# DM1090FFC_MIPI_CAM.net
KiCad netlist of a schematic drawn in Altium Designer
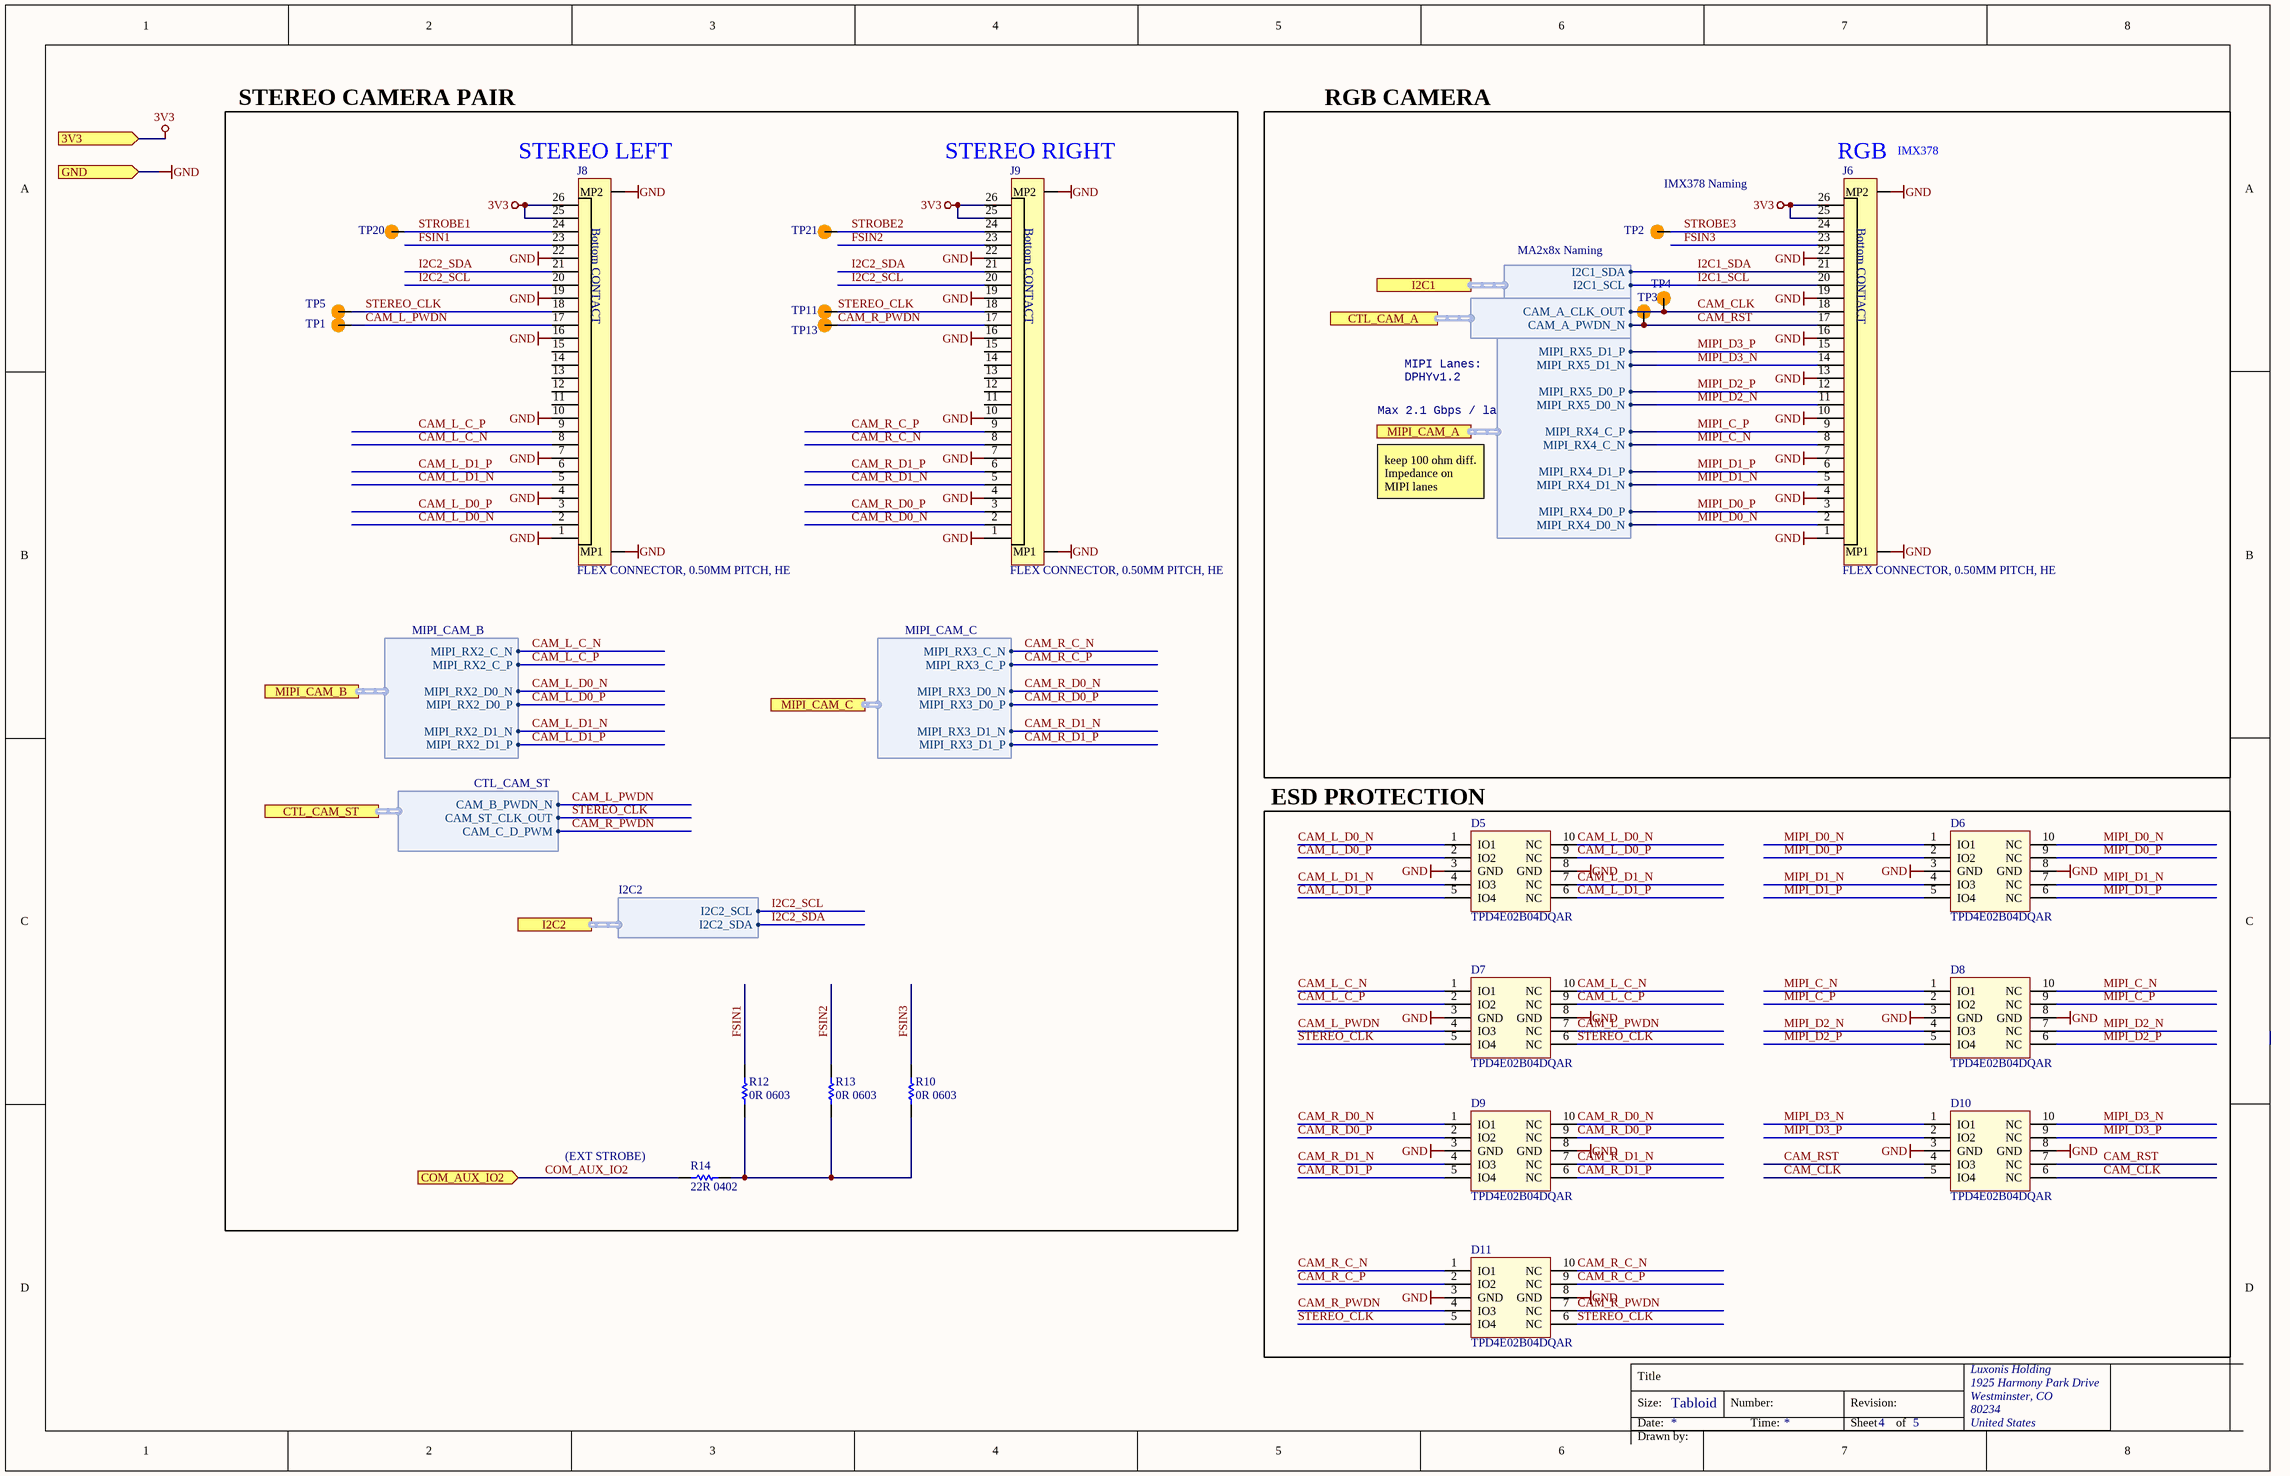
[diagram p0: DM1090FFC_MIPI_CAM.SchDoc]

(export (version "E")
  (design (tool "Eeschema 10.0.6"))
  (components
    (comp (ref "D5")
      (value "TPD4E02B04DQAR")
      (footprint "LuxonisMaster:TPD4E02B04DQAR")
      (libsource (lib "LuxonisMaster") (part "TPD4E02B04DQAR"))
    )
    (comp (ref "D6")
      (value "TPD4E02B04DQAR")
      (footprint "LuxonisMaster:TPD4E02B04DQAR")
      (libsource (lib "LuxonisMaster") (part "TPD4E02B04DQAR"))
    )
    (comp (ref "D7")
      (value "TPD4E02B04DQAR")
      (footprint "LuxonisMaster:TPD4E02B04DQAR")
      (libsource (lib "LuxonisMaster") (part "TPD4E02B04DQAR"))
    )
    (comp (ref "D8")
      (value "TPD4E02B04DQAR")
      (footprint "LuxonisMaster:TPD4E02B04DQAR")
      (libsource (lib "LuxonisMaster") (part "TPD4E02B04DQAR"))
    )
    (comp (ref "D9")
      (value "TPD4E02B04DQAR")
      (footprint "LuxonisMaster:TPD4E02B04DQAR")
      (libsource (lib "LuxonisMaster") (part "TPD4E02B04DQAR"))
    )
    (comp (ref "D10")
      (value "TPD4E02B04DQAR")
      (footprint "LuxonisMaster:TPD4E02B04DQAR")
      (libsource (lib "LuxonisMaster") (part "TPD4E02B04DQAR"))
    )
    (comp (ref "D11")
      (value "TPD4E02B04DQAR")
      (footprint "LuxonisMaster:TPD4E02B04DQAR")
      (libsource (lib "LuxonisMaster") (part "TPD4E02B04DQAR"))
    )
    (comp (ref "J6")
      (value "FLEX CONNECTOR, 0.50MM PITCH, HE")
      (footprint "DM1090FFC:F32R-1A7H1-11026")
      (description "26 Position FFC, FPC Connector Contacts, Bottom 0.020\" (0.50mm) Surface Mount, Right Angle")
      (libsource (lib "DM1090FFC") (part "F32R-1A7H1-11026"))
    )
    (comp (ref "J8")
      (value "FLEX CONNECTOR, 0.50MM PITCH, HE")
      (footprint "DM1090FFC:F32R-1A7H1-11026")
      (description "26 Position FFC, FPC Connector Contacts, Bottom 0.020\" (0.50mm) Surface Mount, Right Angle")
      (libsource (lib "DM1090FFC") (part "F32R-1A7H1-11026"))
    )
    (comp (ref "J9")
      (value "FLEX CONNECTOR, 0.50MM PITCH, HE")
      (footprint "DM1090FFC:F32R-1A7H1-11026")
      (description "26 Position FFC, FPC Connector Contacts, Bottom 0.020\" (0.50mm) Surface Mount, Right Angle")
      (libsource (lib "DM1090FFC") (part "F32R-1A7H1-11026"))
    )
    (comp (ref "R10")
      (value "0R 0603")
      (footprint "RES_Altium_Vault_Generic:RESC0603(1608)_N")
      (fields (field (name "TOLERANCE") "5%"))
      (libsource (lib "LuxonisMaster") (part "CRCW06030000Z0EA"))
    )
    (comp (ref "R12")
      (value "0R 0603")
      (footprint "RES_Altium_Vault_Generic:RESC0603(1608)_N")
      (fields (field (name "TOLERANCE") "5%"))
      (libsource (lib "LuxonisMaster") (part "CRCW06030000Z0EA"))
    )
    (comp (ref "R13")
      (value "0R 0603")
      (footprint "RES_Altium_Vault_Generic:RESC0603(1608)_N")
      (fields (field (name "TOLERANCE") "5%"))
      (libsource (lib "LuxonisMaster") (part "CRCW06030000Z0EA"))
    )
    (comp (ref "R14")
      (value "22R 0402")
      (footprint "RES_Altium_Vault_Generic:RESC0402(1005)_N")
      (description "RES SMD 22 OHM 1% 1/16W 0402")
      (fields (field (name "TOLERANCE") "1%"))
      (libsource (lib "LuxonisMaster") (part "RC0402FR-0722RL"))
    )
    (comp (ref "TP1")
      (value "TP100_200_NS")
      (footprint "LuxonisMaster:TP100_200_NS")
      (libsource (lib "LuxonisMaster") (part "TEST_POINT"))
    )
    (comp (ref "TP2")
      (value "TP100_200_NS")
      (footprint "LuxonisMaster:TP100_200_NS")
      (libsource (lib "LuxonisMaster") (part "TEST_POINT"))
    )
    (comp (ref "TP3")
      (value "TP100_200_NS")
      (footprint "LuxonisMaster:TP100_200_NS")
      (libsource (lib "LuxonisMaster") (part "TEST_POINT"))
    )
    (comp (ref "TP4")
      (value "TP100_200_NS")
      (footprint "LuxonisMaster:TP100_200_NS")
      (libsource (lib "LuxonisMaster") (part "TEST_POINT"))
    )
    (comp (ref "TP5")
      (value "TP100_200_NS")
      (footprint "LuxonisMaster:TP100_200_NS")
      (libsource (lib "LuxonisMaster") (part "TEST_POINT"))
    )
    (comp (ref "TP11")
      (value "TP100_200_NS")
      (footprint "LuxonisMaster:TP100_200_NS")
      (libsource (lib "LuxonisMaster") (part "TEST_POINT"))
    )
    (comp (ref "TP13")
      (value "TP100_200_NS")
      (footprint "LuxonisMaster:TP100_200_NS")
      (libsource (lib "LuxonisMaster") (part "TEST_POINT"))
    )
    (comp (ref "TP20")
      (value "TP100_200_NS")
      (footprint "LuxonisMaster:TP100_200_NS")
      (libsource (lib "LuxonisMaster") (part "TEST_POINT"))
    )
    (comp (ref "TP21")
      (value "TP100_200_NS")
      (footprint "LuxonisMaster:TP100_200_NS")
      (libsource (lib "LuxonisMaster") (part "TEST_POINT"))
    )
  )
  (nets
    (net (code "8") (name "/CAM_CLK") (class "Default")
      (node (ref "D10") (pin "5") (pinfunction "IO4_5") (pintype "passive"))
      (node (ref "D10") (pin "6") (pinfunction "NC_6") (pintype "passive"))
      (node (ref "J6") (pin "18") (pinfunction "18_18") (pintype "passive"))
      (node (ref "TP4") (pin "1") (pintype "passive"))
    )
    (net (code "9") (name "/CAM_L_C_N") (class "Default")
      (node (ref "D7") (pin "1") (pinfunction "IO1_1") (pintype "passive"))
      (node (ref "D7") (pin "10") (pinfunction "NC_10") (pintype "passive"))
      (node (ref "J8") (pin "8") (pinfunction "8_8") (pintype "passive"))
    )
    (net (code "10") (name "/CAM_L_C_P") (class "Default")
      (node (ref "D7") (pin "2") (pinfunction "IO2_2") (pintype "passive"))
      (node (ref "D7") (pin "9") (pinfunction "NC_9") (pintype "passive"))
      (node (ref "J8") (pin "9") (pinfunction "9_9") (pintype "passive"))
    )
    (net (code "11") (name "/CAM_L_D0_N") (class "Default")
      (node (ref "D5") (pin "1") (pinfunction "IO1_1") (pintype "passive"))
      (node (ref "D5") (pin "10") (pinfunction "NC_10") (pintype "passive"))
      (node (ref "J8") (pin "2") (pinfunction "2_2") (pintype "passive"))
    )
    (net (code "12") (name "/CAM_L_D0_P") (class "Default")
      (node (ref "D5") (pin "2") (pinfunction "IO2_2") (pintype "passive"))
      (node (ref "D5") (pin "9") (pinfunction "NC_9") (pintype "passive"))
      (node (ref "J8") (pin "3") (pinfunction "3_3") (pintype "passive"))
    )
    (net (code "13") (name "/CAM_L_D1_N") (class "Default")
      (node (ref "D5") (pin "4") (pinfunction "IO3_4") (pintype "passive"))
      (node (ref "D5") (pin "7") (pinfunction "NC_7") (pintype "passive"))
      (node (ref "J8") (pin "5") (pinfunction "5_5") (pintype "passive"))
    )
    (net (code "14") (name "/CAM_L_D1_P") (class "Default")
      (node (ref "D5") (pin "5") (pinfunction "IO4_5") (pintype "passive"))
      (node (ref "D5") (pin "6") (pinfunction "NC_6") (pintype "passive"))
      (node (ref "J8") (pin "6") (pinfunction "6_6") (pintype "passive"))
    )
    (net (code "15") (name "/CAM_L_PWDN") (class "Default")
      (node (ref "D7") (pin "4") (pinfunction "IO3_4") (pintype "passive"))
      (node (ref "D7") (pin "7") (pinfunction "NC_7") (pintype "passive"))
      (node (ref "J8") (pin "17") (pinfunction "17_17") (pintype "passive"))
      (node (ref "TP1") (pin "1") (pintype "passive"))
    )
    (net (code "16") (name "/CAM_RST") (class "Default")
      (node (ref "D10") (pin "4") (pinfunction "IO3_4") (pintype "passive"))
      (node (ref "D10") (pin "7") (pinfunction "NC_7") (pintype "passive"))
      (node (ref "J6") (pin "17") (pinfunction "17_17") (pintype "passive"))
      (node (ref "TP3") (pin "1") (pintype "passive"))
    )
    (net (code "17") (name "/CAM_R_C_N") (class "Default")
      (node (ref "D11") (pin "1") (pinfunction "IO1_1") (pintype "passive"))
      (node (ref "D11") (pin "10") (pinfunction "NC_10") (pintype "passive"))
      (node (ref "J9") (pin "8") (pinfunction "8_8") (pintype "passive"))
    )
    (net (code "18") (name "/CAM_R_C_P") (class "Default")
      (node (ref "D11") (pin "2") (pinfunction "IO2_2") (pintype "passive"))
      (node (ref "D11") (pin "9") (pinfunction "NC_9") (pintype "passive"))
      (node (ref "J9") (pin "9") (pinfunction "9_9") (pintype "passive"))
    )
    (net (code "19") (name "/CAM_R_D0_N") (class "Default")
      (node (ref "D9") (pin "1") (pinfunction "IO1_1") (pintype "passive"))
      (node (ref "D9") (pin "10") (pinfunction "NC_10") (pintype "passive"))
      (node (ref "J9") (pin "2") (pinfunction "2_2") (pintype "passive"))
    )
    (net (code "20") (name "/CAM_R_D0_P") (class "Default")
      (node (ref "D9") (pin "2") (pinfunction "IO2_2") (pintype "passive"))
      (node (ref "D9") (pin "9") (pinfunction "NC_9") (pintype "passive"))
      (node (ref "J9") (pin "3") (pinfunction "3_3") (pintype "passive"))
    )
    (net (code "21") (name "/CAM_R_D1_N") (class "Default")
      (node (ref "D9") (pin "4") (pinfunction "IO3_4") (pintype "passive"))
      (node (ref "D9") (pin "7") (pinfunction "NC_7") (pintype "passive"))
      (node (ref "J9") (pin "5") (pinfunction "5_5") (pintype "passive"))
    )
    (net (code "22") (name "/CAM_R_D1_P") (class "Default")
      (node (ref "D9") (pin "5") (pinfunction "IO4_5") (pintype "passive"))
      (node (ref "D9") (pin "6") (pinfunction "NC_6") (pintype "passive"))
      (node (ref "J9") (pin "6") (pinfunction "6_6") (pintype "passive"))
    )
    (net (code "23") (name "/CAM_R_PWDN") (class "Default")
      (node (ref "D11") (pin "4") (pinfunction "IO3_4") (pintype "passive"))
      (node (ref "D11") (pin "7") (pinfunction "NC_7") (pintype "passive"))
      (node (ref "J9") (pin "17") (pinfunction "17_17") (pintype "passive"))
      (node (ref "TP13") (pin "1") (pintype "passive"))
    )
    (net (code "24") (name "/COM_AUX_IO2") (class "Default")
      (node (ref "R14") (pin "1") (pinfunction "1_1") (pintype "passive"))
    )
    (net (code "26") (name "/FSIN1") (class "Default")
      (node (ref "J8") (pin "23") (pinfunction "23_23") (pintype "passive"))
      (node (ref "R12") (pin "2") (pinfunction "2_2") (pintype "passive"))
    )
    (net (code "27") (name "/FSIN2") (class "Default")
      (node (ref "J9") (pin "23") (pinfunction "23_23") (pintype "passive"))
      (node (ref "R13") (pin "2") (pinfunction "2_2") (pintype "passive"))
    )
    (net (code "28") (name "/FSIN3") (class "Default")
      (node (ref "J6") (pin "23") (pinfunction "23_23") (pintype "passive"))
      (node (ref "R10") (pin "2") (pinfunction "2_2") (pintype "passive"))
    )
    (net (code "29") (name "/I2C1_SCL") (class "Default")
      (node (ref "J6") (pin "20") (pinfunction "20_20") (pintype "passive"))
    )
    (net (code "30") (name "/I2C1_SDA") (class "Default")
      (node (ref "J6") (pin "21") (pinfunction "21_21") (pintype "passive"))
    )
    (net (code "31") (name "/I2C2_SCL") (class "Default")
      (node (ref "J8") (pin "20") (pinfunction "20_20") (pintype "passive"))
      (node (ref "J9") (pin "20") (pinfunction "20_20") (pintype "passive"))
    )
    (net (code "32") (name "/I2C2_SDA") (class "Default")
      (node (ref "J8") (pin "21") (pinfunction "21_21") (pintype "passive"))
      (node (ref "J9") (pin "21") (pinfunction "21_21") (pintype "passive"))
    )
    (net (code "33") (name "/MIPI_C_N") (class "Default")
      (node (ref "D8") (pin "1") (pinfunction "IO1_1") (pintype "passive"))
      (node (ref "D8") (pin "10") (pinfunction "NC_10") (pintype "passive"))
      (node (ref "J6") (pin "8") (pinfunction "8_8") (pintype "passive"))
    )
    (net (code "34") (name "/MIPI_C_P") (class "Default")
      (node (ref "D8") (pin "2") (pinfunction "IO2_2") (pintype "passive"))
      (node (ref "D8") (pin "9") (pinfunction "NC_9") (pintype "passive"))
      (node (ref "J6") (pin "9") (pinfunction "9_9") (pintype "passive"))
    )
    (net (code "35") (name "/MIPI_D0_N") (class "Default")
      (node (ref "D6") (pin "1") (pinfunction "IO1_1") (pintype "passive"))
      (node (ref "D6") (pin "10") (pinfunction "NC_10") (pintype "passive"))
      (node (ref "J6") (pin "2") (pinfunction "2_2") (pintype "passive"))
    )
    (net (code "36") (name "/MIPI_D0_P") (class "Default")
      (node (ref "D6") (pin "2") (pinfunction "IO2_2") (pintype "passive"))
      (node (ref "D6") (pin "9") (pinfunction "NC_9") (pintype "passive"))
      (node (ref "J6") (pin "3") (pinfunction "3_3") (pintype "passive"))
    )
    (net (code "37") (name "/MIPI_D1_N") (class "Default")
      (node (ref "D6") (pin "4") (pinfunction "IO3_4") (pintype "passive"))
      (node (ref "D6") (pin "7") (pinfunction "NC_7") (pintype "passive"))
      (node (ref "J6") (pin "5") (pinfunction "5_5") (pintype "passive"))
    )
    (net (code "38") (name "/MIPI_D1_P") (class "Default")
      (node (ref "D6") (pin "5") (pinfunction "IO4_5") (pintype "passive"))
      (node (ref "D6") (pin "6") (pinfunction "NC_6") (pintype "passive"))
      (node (ref "J6") (pin "6") (pinfunction "6_6") (pintype "passive"))
    )
    (net (code "39") (name "/MIPI_D2_N") (class "Default")
      (node (ref "D8") (pin "4") (pinfunction "IO3_4") (pintype "passive"))
      (node (ref "D8") (pin "7") (pinfunction "NC_7") (pintype "passive"))
      (node (ref "J6") (pin "11") (pinfunction "11_11") (pintype "passive"))
    )
    (net (code "40") (name "/MIPI_D2_P") (class "Default")
      (node (ref "D8") (pin "5") (pinfunction "IO4_5") (pintype "passive"))
      (node (ref "D8") (pin "6") (pinfunction "NC_6") (pintype "passive"))
      (node (ref "J6") (pin "12") (pinfunction "12_12") (pintype "passive"))
    )
    (net (code "41") (name "/MIPI_D3_N") (class "Default")
      (node (ref "D10") (pin "1") (pinfunction "IO1_1") (pintype "passive"))
      (node (ref "D10") (pin "10") (pinfunction "NC_10") (pintype "passive"))
      (node (ref "J6") (pin "14") (pinfunction "14_14") (pintype "passive"))
    )
    (net (code "42") (name "/MIPI_D3_P") (class "Default")
      (node (ref "D10") (pin "2") (pinfunction "IO2_2") (pintype "passive"))
      (node (ref "D10") (pin "9") (pinfunction "NC_9") (pintype "passive"))
      (node (ref "J6") (pin "15") (pinfunction "15_15") (pintype "passive"))
    )
    (net (code "43") (name "/STEREO_CLK") (class "Default")
      (node (ref "D11") (pin "5") (pinfunction "IO4_5") (pintype "passive"))
      (node (ref "D11") (pin "6") (pinfunction "NC_6") (pintype "passive"))
      (node (ref "D7") (pin "5") (pinfunction "IO4_5") (pintype "passive"))
      (node (ref "D7") (pin "6") (pinfunction "NC_6") (pintype "passive"))
      (node (ref "J8") (pin "18") (pinfunction "18_18") (pintype "passive"))
      (node (ref "J9") (pin "18") (pinfunction "18_18") (pintype "passive"))
      (node (ref "TP11") (pin "1") (pintype "passive"))
      (node (ref "TP5") (pin "1") (pintype "passive"))
    )
    (net (code "44") (name "/STROBE1") (class "Default")
      (node (ref "J8") (pin "24") (pinfunction "24_24") (pintype "passive"))
      (node (ref "TP20") (pin "1") (pintype "passive"))
    )
    (net (code "45") (name "/STROBE2") (class "Default")
      (node (ref "J9") (pin "24") (pinfunction "24_24") (pintype "passive"))
      (node (ref "TP21") (pin "1") (pintype "passive"))
    )
    (net (code "46") (name "/STROBE3") (class "Default")
      (node (ref "J6") (pin "24") (pinfunction "24_24") (pintype "passive"))
      (node (ref "TP2") (pin "1") (pintype "passive"))
    )
    (net (code "53") (name "3V3") (class "Default")
      (node (ref "J6") (pin "25") (pinfunction "25_25") (pintype "passive"))
      (node (ref "J6") (pin "26") (pinfunction "26_26") (pintype "passive"))
      (node (ref "J8") (pin "25") (pinfunction "25_25") (pintype "passive"))
      (node (ref "J8") (pin "26") (pinfunction "26_26") (pintype "passive"))
      (node (ref "J9") (pin "25") (pinfunction "25_25") (pintype "passive"))
      (node (ref "J9") (pin "26") (pinfunction "26_26") (pintype "passive"))
    )
    (net (code "54") (name "GND") (class "Default")
      (node (ref "D10") (pin "3") (pinfunction "GND_3") (pintype "passive"))
      (node (ref "D10") (pin "8") (pinfunction "GND_8") (pintype "passive"))
      (node (ref "D11") (pin "3") (pinfunction "GND_3") (pintype "passive"))
      (node (ref "D11") (pin "8") (pinfunction "GND_8") (pintype "passive"))
      (node (ref "D5") (pin "3") (pinfunction "GND_3") (pintype "passive"))
      (node (ref "D5") (pin "8") (pinfunction "GND_8") (pintype "passive"))
      (node (ref "D6") (pin "3") (pinfunction "GND_3") (pintype "passive"))
      (node (ref "D6") (pin "8") (pinfunction "GND_8") (pintype "passive"))
      (node (ref "D7") (pin "3") (pinfunction "GND_3") (pintype "passive"))
      (node (ref "D7") (pin "8") (pinfunction "GND_8") (pintype "passive"))
      (node (ref "D8") (pin "3") (pinfunction "GND_3") (pintype "passive"))
      (node (ref "D8") (pin "8") (pinfunction "GND_8") (pintype "passive"))
      (node (ref "D9") (pin "3") (pinfunction "GND_3") (pintype "passive"))
      (node (ref "D9") (pin "8") (pinfunction "GND_8") (pintype "passive"))
      (node (ref "J6") (pin "1") (pinfunction "1_1") (pintype "passive"))
      (node (ref "J6") (pin "10") (pinfunction "10_10") (pintype "passive"))
      (node (ref "J6") (pin "13") (pinfunction "13_13") (pintype "passive"))
      (node (ref "J6") (pin "16") (pinfunction "16_16") (pintype "passive"))
      (node (ref "J6") (pin "19") (pinfunction "19_19") (pintype "passive"))
      (node (ref "J6") (pin "22") (pinfunction "22_22") (pintype "passive"))
      (node (ref "J6") (pin "4") (pinfunction "4_4") (pintype "passive"))
      (node (ref "J6") (pin "7") (pinfunction "7_7") (pintype "passive"))
      (node (ref "J6") (pin "MP1") (pinfunction "MP1_MP1") (pintype "passive"))
      (node (ref "J6") (pin "MP2") (pinfunction "MP2_MP2") (pintype "passive"))
      (node (ref "J8") (pin "1") (pinfunction "1_1") (pintype "passive"))
      (node (ref "J8") (pin "10") (pinfunction "10_10") (pintype "passive"))
      (node (ref "J8") (pin "16") (pinfunction "16_16") (pintype "passive"))
      (node (ref "J8") (pin "19") (pinfunction "19_19") (pintype "passive"))
      (node (ref "J8") (pin "22") (pinfunction "22_22") (pintype "passive"))
      (node (ref "J8") (pin "4") (pinfunction "4_4") (pintype "passive"))
      (node (ref "J8") (pin "7") (pinfunction "7_7") (pintype "passive"))
      (node (ref "J8") (pin "MP1") (pinfunction "MP1_MP1") (pintype "passive"))
      (node (ref "J8") (pin "MP2") (pinfunction "MP2_MP2") (pintype "passive"))
      (node (ref "J9") (pin "1") (pinfunction "1_1") (pintype "passive"))
      (node (ref "J9") (pin "10") (pinfunction "10_10") (pintype "passive"))
      (node (ref "J9") (pin "16") (pinfunction "16_16") (pintype "passive"))
      (node (ref "J9") (pin "19") (pinfunction "19_19") (pintype "passive"))
      (node (ref "J9") (pin "22") (pinfunction "22_22") (pintype "passive"))
      (node (ref "J9") (pin "4") (pinfunction "4_4") (pintype "passive"))
      (node (ref "J9") (pin "7") (pinfunction "7_7") (pintype "passive"))
      (node (ref "J9") (pin "MP1") (pinfunction "MP1_MP1") (pintype "passive"))
      (node (ref "J9") (pin "MP2") (pinfunction "MP2_MP2") (pintype "passive"))
    )
    (net (code "55") (name "Net-(R10-Pad1)") (class "Default")
      (node (ref "R10") (pin "1") (pinfunction "1_1") (pintype "passive"))
      (node (ref "R12") (pin "1") (pinfunction "1_1") (pintype "passive"))
      (node (ref "R13") (pin "1") (pinfunction "1_1") (pintype "passive"))
      (node (ref "R14") (pin "2") (pinfunction "2_2") (pintype "passive"))
    )
    (net (code "56") (name "unconnected-(J8-Pad11)") (class "Default")
      (node (ref "J8") (pin "11") (pinfunction "11_11") (pintype "passive"))
    )
    (net (code "57") (name "unconnected-(J8-Pad12)") (class "Default")
      (node (ref "J8") (pin "12") (pinfunction "12_12") (pintype "passive"))
    )
    (net (code "58") (name "unconnected-(J8-Pad13)") (class "Default")
      (node (ref "J8") (pin "13") (pinfunction "13_13") (pintype "passive"))
    )
    (net (code "59") (name "unconnected-(J8-Pad14)") (class "Default")
      (node (ref "J8") (pin "14") (pinfunction "14_14") (pintype "passive"))
    )
    (net (code "60") (name "unconnected-(J8-Pad15)") (class "Default")
      (node (ref "J8") (pin "15") (pinfunction "15_15") (pintype "passive"))
    )
    (net (code "61") (name "unconnected-(J9-Pad11)") (class "Default")
      (node (ref "J9") (pin "11") (pinfunction "11_11") (pintype "passive"))
    )
    (net (code "62") (name "unconnected-(J9-Pad12)") (class "Default")
      (node (ref "J9") (pin "12") (pinfunction "12_12") (pintype "passive"))
    )
    (net (code "63") (name "unconnected-(J9-Pad13)") (class "Default")
      (node (ref "J9") (pin "13") (pinfunction "13_13") (pintype "passive"))
    )
    (net (code "64") (name "unconnected-(J9-Pad14)") (class "Default")
      (node (ref "J9") (pin "14") (pinfunction "14_14") (pintype "passive"))
    )
    (net (code "65") (name "unconnected-(J9-Pad15)") (class "Default")
      (node (ref "J9") (pin "15") (pinfunction "15_15") (pintype "passive"))
    )
  )
)
